# usb-power-switch.net
KiCad netlist of a schematic drawn in EAGLE
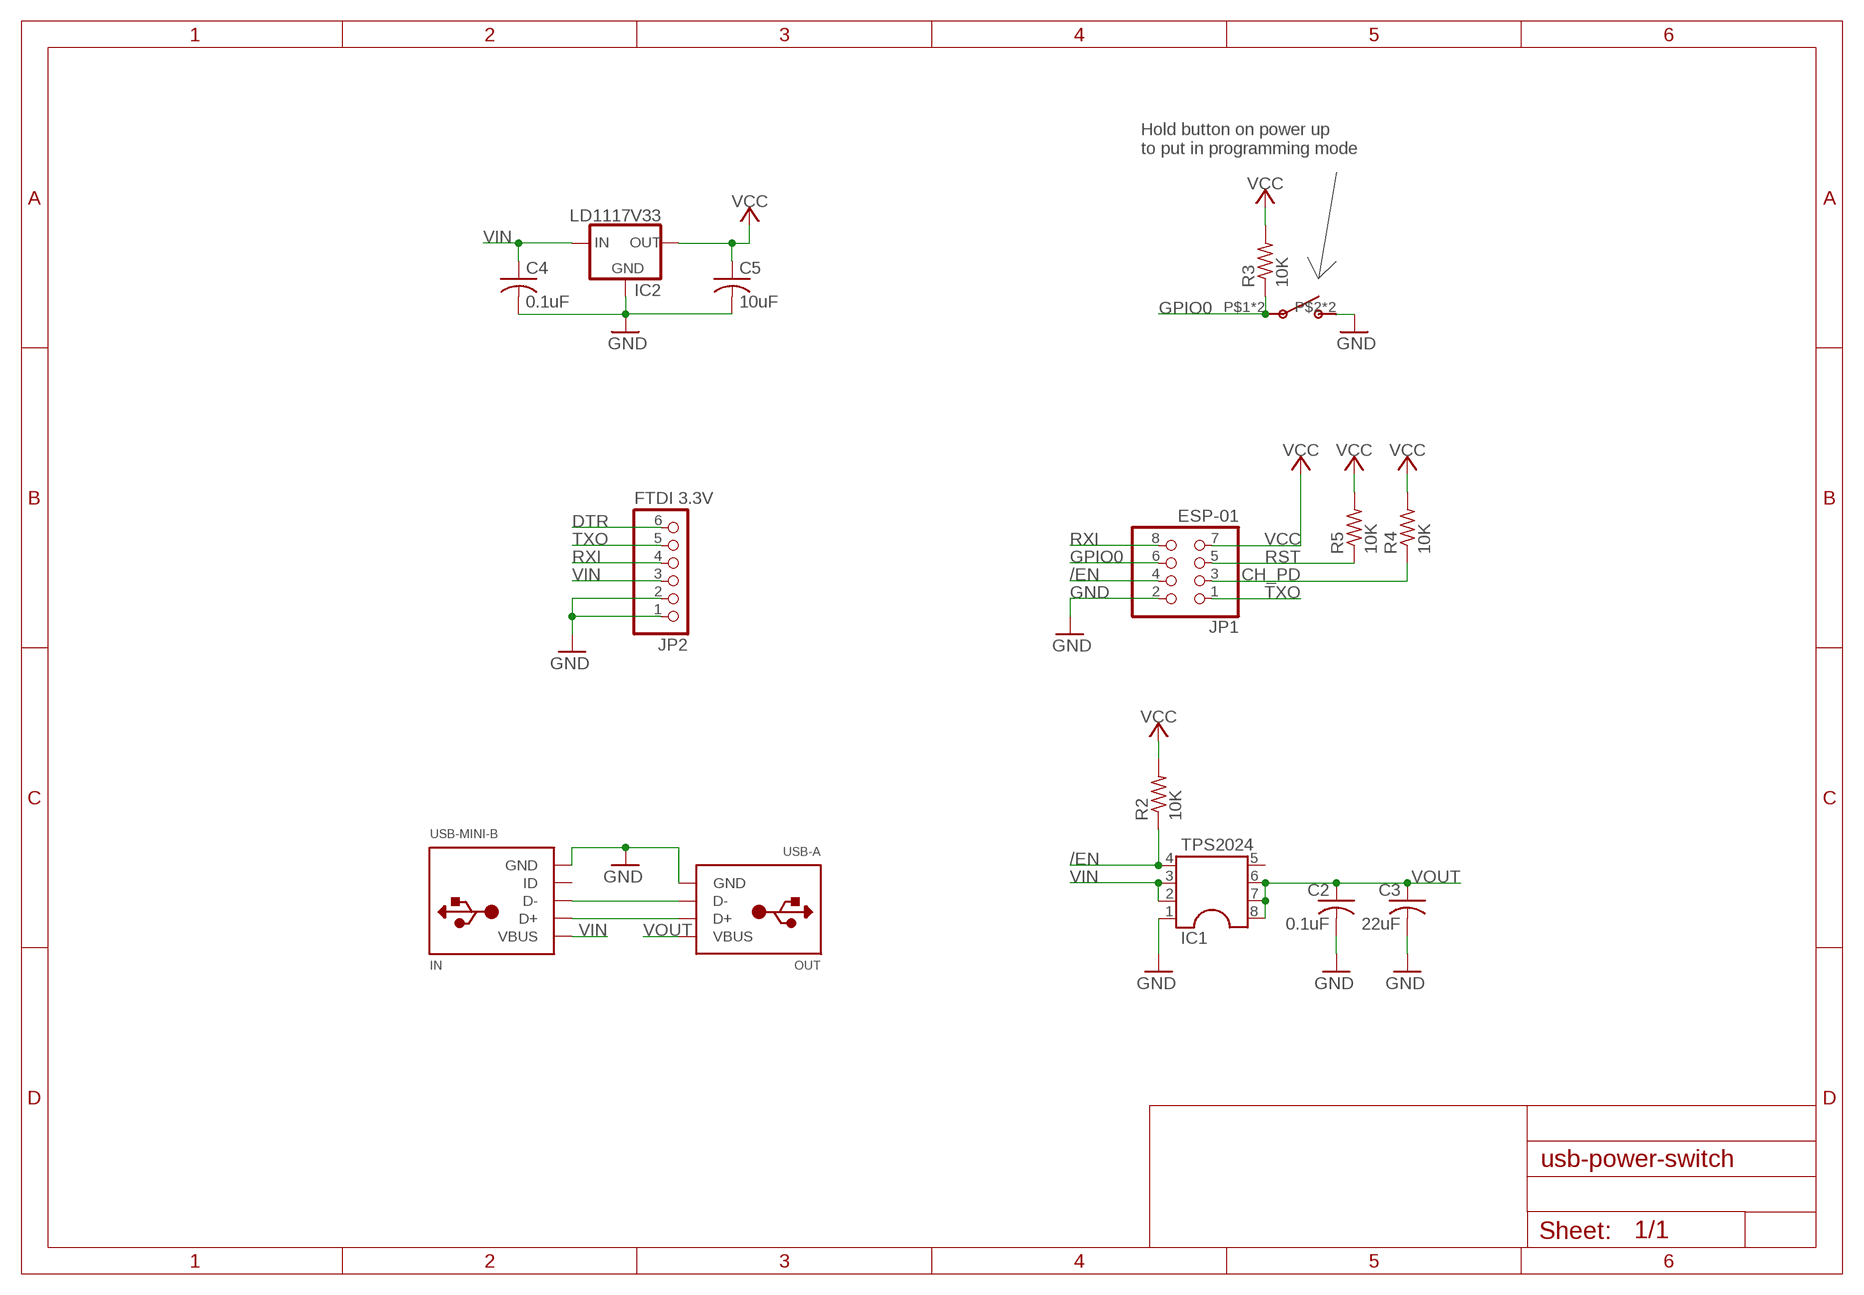
[diagram p0: schematic, sheet 1]

(export (version "E")
  (design (tool "Eeschema 10.0.6"))
  (components
    (comp (ref "C2")
      (value "0.1uF")
      (footprint "eagle-import:C025-025X050")
      (libsource (lib "eagle-import") (part "C-US025-025X050"))
    )
    (comp (ref "C3")
      (value "22uF")
      (footprint "eagle-import:C025-025X050")
      (libsource (lib "eagle-import") (part "C-US025-025X050"))
    )
    (comp (ref "C4")
      (value "0.1uF")
      (footprint "eagle-import:C025-025X050")
      (libsource (lib "eagle-import") (part "C-US025-025X050"))
    )
    (comp (ref "C5")
      (value "10uF")
      (footprint "eagle-import:C025-025X050")
      (libsource (lib "eagle-import") (part "C-US025-025X050"))
    )
    (comp (ref "IC1")
      (value "TPS2024")
      (footprint "eagle-import:DIL08")
      (libsource (lib "eagle-import") (part "DIL8"))
    )
    (comp (ref "IC2")
      (value "LD1117V33")
      (footprint "eagle-import:78XXL")
      (libsource (lib "eagle-import") (part "V_REG_LD1117VXX"))
    )
    (comp (ref "IN")
      (value "USB-MINI-B")
      (footprint "eagle-import:USB-MINI-B")
      (libsource (lib "eagle-import") (part "USB-MINI-B"))
    )
    (comp (ref "JP1")
      (value "ESP-01")
      (footprint "eagle-import:2X04")
      (libsource (lib "eagle-import") (part "PINHD-2X4"))
    )
    (comp (ref "JP2")
      (value "FTDI 3.3V")
      (footprint "eagle-import:1X06")
      (libsource (lib "eagle-import") (part "PINHD-1X6"))
    )
    (comp (ref "OUT")
      (value "USB-A")
      (footprint "eagle-import:USB-A")
      (libsource (lib "eagle-import") (part "USB-A"))
    )
    (comp (ref "R2")
      (value "10K")
      (footprint "eagle-import:0207_10")
      (libsource (lib "eagle-import") (part "R-US_0207/10"))
    )
    (comp (ref "R3")
      (value "10K")
      (footprint "eagle-import:0207_10")
      (libsource (lib "eagle-import") (part "R-US_0207/10"))
    )
    (comp (ref "R4")
      (value "10K")
      (footprint "eagle-import:0207_10")
      (libsource (lib "eagle-import") (part "R-US_0207/10"))
    )
    (comp (ref "R5")
      (value "10K")
      (footprint "eagle-import:0207_10")
      (libsource (lib "eagle-import") (part "R-US_0207/10"))
    )
    (comp (ref "S1")
      (value "TACTILE-BUTTON-MJTP1230")
      (footprint "eagle-import:TACTILE-BUTTON-MJTP1230")
      (libsource (lib "eagle-import") (part "TACTILE-BUTTON-MJTP1230"))
    )
  )
  (nets
    (net (code "1") (name "/CH_PD") (class "Default")
      (node (ref "JP1") (pin "3") (pinfunction "3_3") (pintype "passive"))
      (node (ref "R4") (pin "1") (pinfunction "1_1") (pintype "passive"))
    )
    (net (code "2") (name "/DTR") (class "Default")
      (node (ref "JP2") (pin "6") (pinfunction "6_6") (pintype "passive"))
    )
    (net (code "3") (name "/GPIO0") (class "Default")
      (node (ref "JP1") (pin "6") (pinfunction "6_6") (pintype "passive"))
      (node (ref "R3") (pin "1") (pinfunction "1_1") (pintype "passive"))
      (node (ref "S1") (pin "P$1") (pinfunction "1_P$1") (pintype "passive"))
      (node (ref "S1") (pin "P$3") (pinfunction "1_P$3") (pintype "passive"))
    )
    (net (code "4") (name "/RST") (class "Default")
      (node (ref "JP1") (pin "5") (pinfunction "5_5") (pintype "passive"))
      (node (ref "R5") (pin "1") (pinfunction "1_1") (pintype "passive"))
    )
    (net (code "5") (name "/RXI") (class "Default")
      (node (ref "JP1") (pin "8") (pinfunction "8_8") (pintype "passive"))
      (node (ref "JP2") (pin "4") (pinfunction "4_4") (pintype "passive"))
    )
    (net (code "6") (name "/TXO") (class "Default")
      (node (ref "JP1") (pin "1") (pinfunction "1_1") (pintype "passive"))
      (node (ref "JP2") (pin "5") (pinfunction "5_5") (pintype "passive"))
    )
    (net (code "7") (name "/VIN") (class "Default")
      (node (ref "C4") (pin "1") (pinfunction "1_1") (pintype "passive"))
      (node (ref "IC1") (pin "2") (pinfunction "2_2") (pintype "passive"))
      (node (ref "IC1") (pin "3") (pinfunction "3_3") (pintype "passive"))
      (node (ref "IC2") (pin "OUT") (pinfunction "IN_OUT") (pintype "input"))
      (node (ref "IN") (pin "VBUS") (pinfunction "VBUS_VBUS") (pintype "power_in"))
      (node (ref "JP2") (pin "3") (pinfunction "3_3") (pintype "passive"))
    )
    (net (code "8") (name "/VOUT") (class "Default")
      (node (ref "C2") (pin "1") (pinfunction "1_1") (pintype "passive"))
      (node (ref "C3") (pin "1") (pinfunction "1_1") (pintype "passive"))
      (node (ref "IC1") (pin "6") (pinfunction "6_6") (pintype "passive"))
      (node (ref "IC1") (pin "7") (pinfunction "7_7") (pintype "passive"))
      (node (ref "IC1") (pin "8") (pinfunction "8_8") (pintype "passive"))
      (node (ref "OUT") (pin "P$1") (pinfunction "VBUS_P$1") (pintype "power_in"))
    )
    (net (code "9") (name "/{slash}EN") (class "Default")
      (node (ref "IC1") (pin "4") (pinfunction "4_4") (pintype "passive"))
      (node (ref "JP1") (pin "4") (pinfunction "4_4") (pintype "passive"))
      (node (ref "R2") (pin "1") (pinfunction "1_1") (pintype "passive"))
    )
    (net (code "10") (name "GND") (class "Default")
      (node (ref "C2") (pin "2") (pinfunction "2_2") (pintype "passive"))
      (node (ref "C3") (pin "2") (pinfunction "2_2") (pintype "passive"))
      (node (ref "C4") (pin "2") (pinfunction "2_2") (pintype "passive"))
      (node (ref "C5") (pin "2") (pinfunction "2_2") (pintype "passive"))
      (node (ref "IC1") (pin "1") (pinfunction "1_1") (pintype "passive"))
      (node (ref "IC2") (pin "IN") (pinfunction "GND_IN") (pintype "input"))
      (node (ref "IN") (pin "GND") (pinfunction "GND_GND") (pintype "power_in"))
      (node (ref "JP1") (pin "2") (pinfunction "2_2") (pintype "passive"))
      (node (ref "JP2") (pin "1") (pinfunction "1_1") (pintype "passive"))
      (node (ref "JP2") (pin "2") (pinfunction "2_2") (pintype "passive"))
      (node (ref "OUT") (pin "P$4") (pinfunction "GND_P$4") (pintype "power_in"))
      (node (ref "S1") (pin "P$2") (pinfunction "3_P$2") (pintype "passive"))
      (node (ref "S1") (pin "P$4") (pinfunction "3_P$4") (pintype "passive"))
    )
    (net (code "11") (name "Net-(OUT-D+)") (class "Default")
      (node (ref "IN") (pin "D+") (pinfunction "D+_D+") (pintype "bidirectional"))
      (node (ref "OUT") (pin "P$3") (pinfunction "D+_P$3") (pintype "bidirectional"))
    )
    (net (code "12") (name "Net-(OUT-D-)") (class "Default")
      (node (ref "IN") (pin "D-") (pinfunction "D-_D-") (pintype "bidirectional"))
      (node (ref "OUT") (pin "P$2") (pinfunction "D-_P$2") (pintype "bidirectional"))
    )
    (net (code "13") (name "VCC") (class "Default")
      (node (ref "C5") (pin "1") (pinfunction "1_1") (pintype "passive"))
      (node (ref "IC2") (pin "GND") (pinfunction "OUT_GND") (pintype "passive"))
      (node (ref "JP1") (pin "7") (pinfunction "7_7") (pintype "passive"))
      (node (ref "R2") (pin "2") (pinfunction "2_2") (pintype "passive"))
      (node (ref "R3") (pin "2") (pinfunction "2_2") (pintype "passive"))
      (node (ref "R4") (pin "2") (pinfunction "2_2") (pintype "passive"))
      (node (ref "R5") (pin "2") (pinfunction "2_2") (pintype "passive"))
    )
    (net (code "14") (name "unconnected-(IC1-Pad5)") (class "Default")
      (node (ref "IC1") (pin "5") (pinfunction "5_5") (pintype "passive"))
    )
    (net (code "15") (name "unconnected-(IN-PadID)") (class "Default")
      (node (ref "IN") (pin "ID") (pinfunction "ID_ID") (pintype "bidirectional"))
    )
  )
)
